# RJ45-LED-Breakout.net
KiCad netlist of a schematic drawn in EAGLE
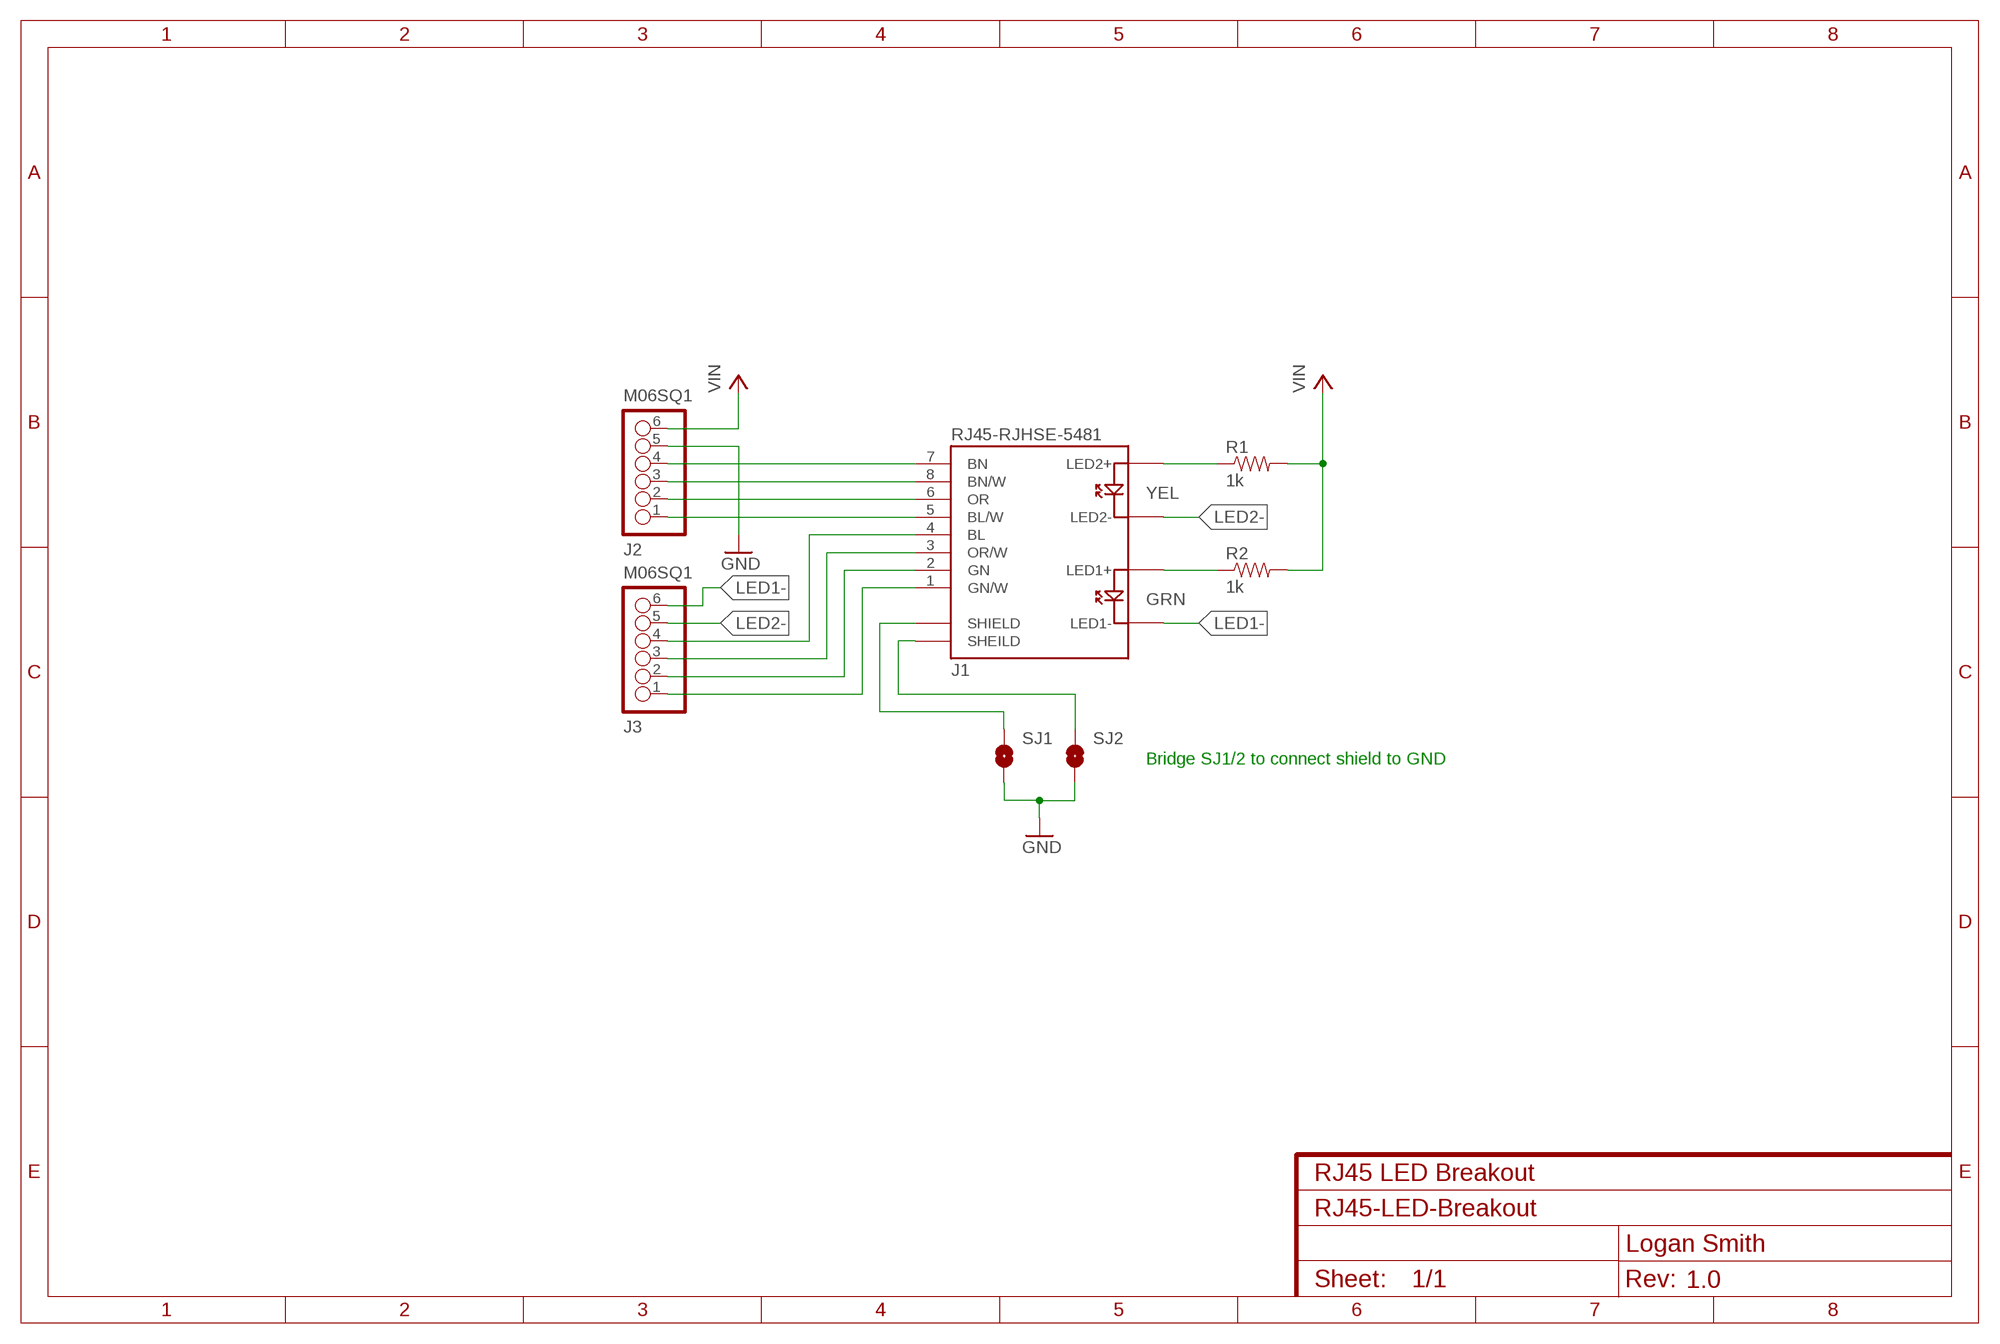
[diagram p0: schematic, sheet 1]

(export (version "E")
  (design (tool "Eeschema 10.0.6"))
  (components
    (comp (ref "J1")
      (value "RJ45-RJHSE-5481")
      (footprint "eagle-import:RJ45-RJHSE")
      (libsource (lib "eagle-import") (part "RJ45-RJHSE-5481"))
    )
    (comp (ref "J2")
      (value "M06SQ1")
      (footprint "eagle-import:1X06_SQ1")
      (libsource (lib "eagle-import") (part "M06?SQ1"))
    )
    (comp (ref "J3")
      (value "M06SQ1")
      (footprint "eagle-import:1X06_SQ1")
      (libsource (lib "eagle-import") (part "M06?SQ1"))
    )
    (comp (ref "R1")
      (value "1k")
      (footprint "eagle-import:0805-RES")
      (fields
        (field (name "MFR") "Panasonic Electronic Components")
        (field (name "MPN") "ERJ-6GEYJ102V")
        (field (name "POWER") "0.125W")
      )
      (libsource (lib "eagle-import") (part "1K--?08055%"))
    )
    (comp (ref "R2")
      (value "1k")
      (footprint "eagle-import:0805-RES")
      (fields
        (field (name "MFR") "Panasonic Electronic Components")
        (field (name "MPN") "ERJ-6GEYJ102V")
        (field (name "POWER") "0.125W")
      )
      (libsource (lib "eagle-import") (part "1K--?08055%"))
    )
    (comp (ref "SJ1")
      (value "SJ_1WAY")
      (footprint "eagle-import:SJ_2")
      (libsource (lib "eagle-import") (part "SJ_1WAY"))
    )
    (comp (ref "SJ2")
      (value "SJ_1WAY")
      (footprint "eagle-import:SJ_2")
      (libsource (lib "eagle-import") (part "SJ_1WAY"))
    )
  )
  (nets
    (net (code "1") (name "GND") (class "Default")
      (node (ref "J2") (pin "5") (pinfunction "5_5") (pintype "bidirectional"))
      (node (ref "SJ1") (pin "2") (pinfunction "2_2") (pintype "passive"))
      (node (ref "SJ2") (pin "2") (pinfunction "2_2") (pintype "passive"))
    )
    (net (code "2") (name "LED1-") (class "Default")
      (node (ref "J1") (pin "LE1D-") (pinfunction "LED1-_LE1D-") (pintype "bidirectional"))
      (node (ref "J3") (pin "6") (pinfunction "6_6") (pintype "bidirectional"))
    )
    (net (code "3") (name "LED2-") (class "Default")
      (node (ref "J1") (pin "LED2-") (pinfunction "LED2-_LED2-") (pintype "bidirectional"))
      (node (ref "J3") (pin "5") (pinfunction "5_5") (pintype "bidirectional"))
    )
    (net (code "4") (name "Net-(J1-BL)") (class "Default")
      (node (ref "J1") (pin "4") (pinfunction "BL_4") (pintype "bidirectional"))
      (node (ref "J3") (pin "4") (pinfunction "4_4") (pintype "bidirectional"))
    )
    (net (code "5") (name "Net-(J1-BL{slash}W)") (class "Default")
      (node (ref "J1") (pin "5") (pinfunction "BL/W_5") (pintype "bidirectional"))
      (node (ref "J2") (pin "1") (pinfunction "1_1") (pintype "bidirectional"))
    )
    (net (code "6") (name "Net-(J1-BN)") (class "Default")
      (node (ref "J1") (pin "7") (pinfunction "BN_7") (pintype "bidirectional"))
      (node (ref "J2") (pin "4") (pinfunction "4_4") (pintype "bidirectional"))
    )
    (net (code "7") (name "Net-(J1-BN{slash}W)") (class "Default")
      (node (ref "J1") (pin "8") (pinfunction "BN/W_8") (pintype "bidirectional"))
      (node (ref "J2") (pin "3") (pinfunction "3_3") (pintype "bidirectional"))
    )
    (net (code "8") (name "Net-(J1-GN)") (class "Default")
      (node (ref "J1") (pin "2") (pinfunction "GN_2") (pintype "bidirectional"))
      (node (ref "J3") (pin "2") (pinfunction "2_2") (pintype "bidirectional"))
    )
    (net (code "9") (name "Net-(J1-GN{slash}W)") (class "Default")
      (node (ref "J1") (pin "1") (pinfunction "GN/W_1") (pintype "bidirectional"))
      (node (ref "J3") (pin "1") (pinfunction "1_1") (pintype "bidirectional"))
    )
    (net (code "10") (name "Net-(J1-OR)") (class "Default")
      (node (ref "J1") (pin "6") (pinfunction "OR_6") (pintype "bidirectional"))
      (node (ref "J2") (pin "2") (pinfunction "2_2") (pintype "bidirectional"))
    )
    (net (code "11") (name "Net-(J1-OR{slash}W)") (class "Default")
      (node (ref "J1") (pin "3") (pinfunction "OR/W_3") (pintype "bidirectional"))
      (node (ref "J3") (pin "3") (pinfunction "3_3") (pintype "bidirectional"))
    )
    (net (code "12") (name "Net-(J1-SHEILD)") (class "Default")
      (node (ref "J1") (pin "SHEILD@1") (pinfunction "SHEILD_SHEILD@1") (pintype "bidirectional"))
      (node (ref "SJ2") (pin "1") (pinfunction "1_1") (pintype "passive"))
    )
    (net (code "13") (name "Net-(J1-SHIELD)") (class "Default")
      (node (ref "J1") (pin "SHIELD@0") (pinfunction "SHIELD_SHIELD@0") (pintype "bidirectional"))
      (node (ref "SJ1") (pin "1") (pinfunction "1_1") (pintype "passive"))
    )
    (net (code "14") (name "Net-(R1-1)") (class "Default")
      (node (ref "J1") (pin "LED2+") (pinfunction "LED2+_LED2+") (pintype "bidirectional"))
      (node (ref "R1") (pin "P$1") (pinfunction "1_P$1") (pintype "passive"))
    )
    (net (code "15") (name "Net-(R2-1)") (class "Default")
      (node (ref "J1") (pin "LED1+") (pinfunction "LED1+_LED1+") (pintype "bidirectional"))
      (node (ref "R2") (pin "P$1") (pinfunction "1_P$1") (pintype "passive"))
    )
    (net (code "16") (name "VIN") (class "Default")
      (node (ref "J2") (pin "6") (pinfunction "6_6") (pintype "bidirectional"))
      (node (ref "R1") (pin "P$2") (pinfunction "2_P$2") (pintype "passive"))
      (node (ref "R2") (pin "P$2") (pinfunction "2_P$2") (pintype "passive"))
    )
  )
)
